# overall_circuit.net
KiCad netlist of a schematic drawn in EAGLE
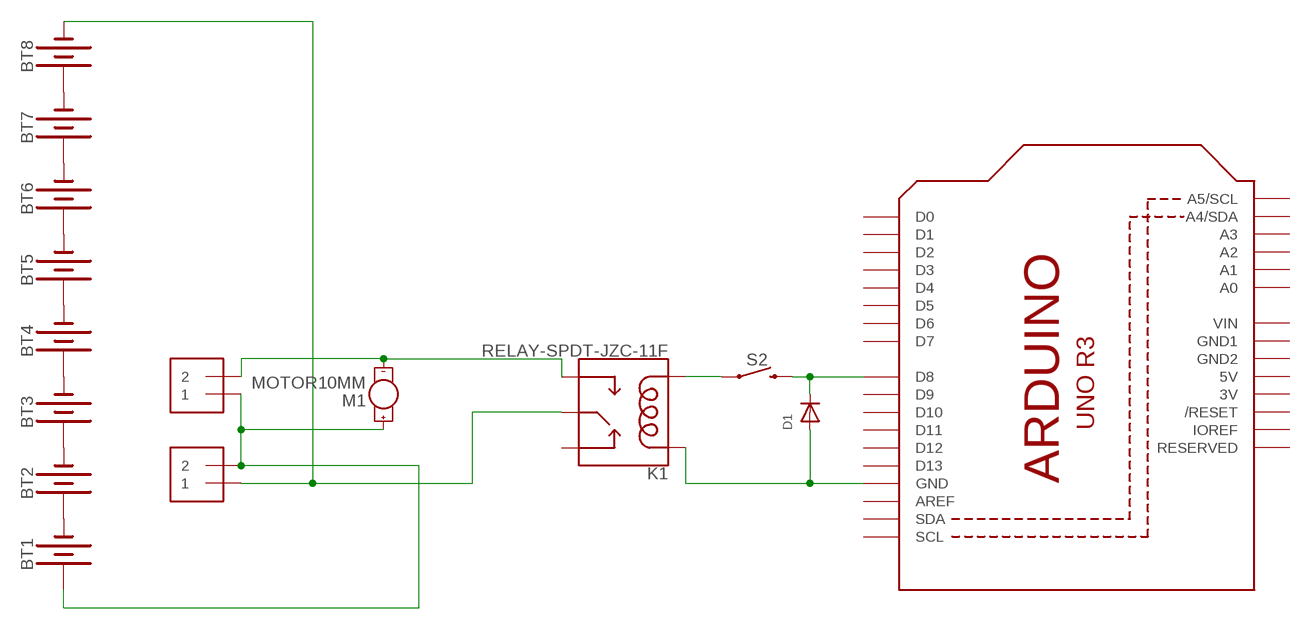
[diagram p0: schematic, sheet 1]

(export (version "E")
  (design (tool "Eeschema 10.0.6"))
  (components
    (comp (ref "BT1")
      (value "BATTERY-9V")
      (footprint "eagle-import:BATTCON_9V")
      (libsource (lib "eagle-import") (part "BATTERY-9V"))
    )
    (comp (ref "BT2")
      (value "BATTERY-9V")
      (footprint "eagle-import:BATTCON_9V")
      (libsource (lib "eagle-import") (part "BATTERY-9V"))
    )
    (comp (ref "BT3")
      (value "BATTERY-9V")
      (footprint "eagle-import:BATTCON_9V")
      (libsource (lib "eagle-import") (part "BATTERY-9V"))
    )
    (comp (ref "BT4")
      (value "BATTERY-9V")
      (footprint "eagle-import:BATTCON_9V")
      (libsource (lib "eagle-import") (part "BATTERY-9V"))
    )
    (comp (ref "BT5")
      (value "BATTERY-9V")
      (footprint "eagle-import:BATTCON_9V")
      (libsource (lib "eagle-import") (part "BATTERY-9V"))
    )
    (comp (ref "BT6")
      (value "BATTERY-9V")
      (footprint "eagle-import:BATTCON_9V")
      (libsource (lib "eagle-import") (part "BATTERY-9V"))
    )
    (comp (ref "BT7")
      (value "BATTERY-9V")
      (footprint "eagle-import:BATTCON_9V")
      (libsource (lib "eagle-import") (part "BATTERY-9V"))
    )
    (comp (ref "BT8")
      (value "BATTERY-9V")
      (footprint "eagle-import:BATTCON_9V")
      (libsource (lib "eagle-import") (part "BATTERY-9V"))
    )
    (comp (ref "D1")
      (value "DIODEDO-1N4148")
      (footprint "eagle-import:DO-1N4148")
      (libsource (lib "eagle-import") (part "DIODEDO-1N4148"))
    )
    (comp (ref "J1")
      (value "1X2-3.5MM")
      (footprint "eagle-import:1X2-3.5MM")
      (libsource (lib "eagle-import") (part "1X2-3.5MM"))
    )
    (comp (ref "J2")
      (value "1X2-3.5MM")
      (footprint "eagle-import:1X2-3.5MM")
      (libsource (lib "eagle-import") (part "1X2-3.5MM"))
    )
    (comp (ref "K1")
      (value "RELAY-SPDT-JZC-11F")
      (footprint "eagle-import:RELAY-JZC")
      (libsource (lib "eagle-import") (part "RELAY-SPDT-JZC-11F"))
    )
    (comp (ref "M1")
      (value "MOTOR10MM")
      (footprint "eagle-import:VIBE-MOTOR-10MM")
      (libsource (lib "eagle-import") (part "MOTOR10MM"))
    )
    (comp (ref "S2")
      (value "MOMENTARY-SWITCH-SPST-SMD-5.2MM")
      (footprint "eagle-import:TACTILE_SWITCH_SMD_5.2MM")
      (libsource (lib "eagle-import") (part "MOMENTARY-SWITCH-SPST-SMD-5.2MM"))
    )
    (comp (ref "U1")
      (value "ARDUINOR3-DIMENSION")
      (footprint "eagle-import:ARDUINOR3")
      (libsource (lib "eagle-import") (part "ARDUINOR3-DIMENSION"))
    )
  )
  (nets
    (net (code "1") (name "/3V") (class "Default")
      (node (ref "U1") (pin "3V") (pinfunction "3V_3V") (pintype "power_in"))
    )
    (net (code "2") (name "/5V") (class "Default")
      (node (ref "U1") (pin "5V") (pinfunction "5V_5V") (pintype "power_in"))
    )
    (net (code "3") (name "/GND1") (class "Default")
      (node (ref "U1") (pin "GND1") (pinfunction "GND1_GND1") (pintype "power_in"))
    )
    (net (code "4") (name "/GND2") (class "Default")
      (node (ref "U1") (pin "GND2") (pinfunction "GND2_GND2") (pintype "power_in"))
    )
    (net (code "5") (name "/VIN") (class "Default")
      (node (ref "U1") (pin "VIN") (pinfunction "VIN_VIN") (pintype "power_in"))
    )
    (net (code "6") (name "Net-(BT1-Pad+)") (class "Default")
      (node (ref "BT1") (pin "+") (pinfunction "+_+") (pintype "power_in"))
      (node (ref "J1") (pin "1") (pinfunction "1_1") (pintype "passive"))
      (node (ref "J2") (pin "2") (pinfunction "2_2") (pintype "passive"))
      (node (ref "M1") (pin "+") (pinfunction "+_+") (pintype "bidirectional"))
    )
    (net (code "7") (name "Net-(BT1-Pad-)") (class "Default")
      (node (ref "BT1") (pin "-") (pinfunction "-_-") (pintype "power_in"))
      (node (ref "BT2") (pin "+") (pinfunction "+_+") (pintype "power_in"))
    )
    (net (code "8") (name "Net-(BT2-Pad-)") (class "Default")
      (node (ref "BT2") (pin "-") (pinfunction "-_-") (pintype "power_in"))
      (node (ref "BT3") (pin "+") (pinfunction "+_+") (pintype "power_in"))
    )
    (net (code "9") (name "Net-(BT3-Pad-)") (class "Default")
      (node (ref "BT3") (pin "-") (pinfunction "-_-") (pintype "power_in"))
      (node (ref "BT4") (pin "+") (pinfunction "+_+") (pintype "power_in"))
    )
    (net (code "10") (name "Net-(BT4-Pad-)") (class "Default")
      (node (ref "BT4") (pin "-") (pinfunction "-_-") (pintype "power_in"))
      (node (ref "BT5") (pin "+") (pinfunction "+_+") (pintype "power_in"))
    )
    (net (code "11") (name "Net-(BT5-Pad-)") (class "Default")
      (node (ref "BT5") (pin "-") (pinfunction "-_-") (pintype "power_in"))
      (node (ref "BT6") (pin "+") (pinfunction "+_+") (pintype "power_in"))
    )
    (net (code "12") (name "Net-(BT6-Pad-)") (class "Default")
      (node (ref "BT6") (pin "-") (pinfunction "-_-") (pintype "power_in"))
      (node (ref "BT7") (pin "+") (pinfunction "+_+") (pintype "power_in"))
    )
    (net (code "13") (name "Net-(BT7-Pad-)") (class "Default")
      (node (ref "BT7") (pin "-") (pinfunction "-_-") (pintype "power_in"))
      (node (ref "BT8") (pin "+") (pinfunction "+_+") (pintype "power_in"))
    )
    (net (code "14") (name "Net-(K1-COIL1)") (class "Default")
      (node (ref "D1") (pin "A") (pinfunction "A_A") (pintype "passive"))
      (node (ref "K1") (pin "5") (pinfunction "COIL1_5") (pintype "bidirectional"))
      (node (ref "U1") (pin "GND") (pinfunction "GND_GND") (pintype "power_in"))
    )
    (net (code "15") (name "Net-(K1-COIL2)") (class "Default")
      (node (ref "K1") (pin "1") (pinfunction "COIL2_1") (pintype "bidirectional"))
      (node (ref "S2") (pin "1") (pinfunction "1_1") (pintype "passive"))
    )
    (net (code "16") (name "Net-(K1-MAIN)") (class "Default")
      (node (ref "BT8") (pin "-") (pinfunction "-_-") (pintype "power_in"))
      (node (ref "J2") (pin "1") (pinfunction "1_1") (pintype "passive"))
      (node (ref "K1") (pin "4") (pinfunction "MAIN_4") (pintype "bidirectional"))
    )
    (net (code "17") (name "Net-(K1-NO)") (class "Default")
      (node (ref "J1") (pin "2") (pinfunction "2_2") (pintype "passive"))
      (node (ref "K1") (pin "3") (pinfunction "NO_3") (pintype "bidirectional"))
      (node (ref "M1") (pin "-") (pinfunction "-_-") (pintype "bidirectional"))
    )
    (net (code "18") (name "Net-(S2-2)") (class "Default")
      (node (ref "D1") (pin "C") (pinfunction "C_C") (pintype "passive"))
      (node (ref "S2") (pin "3") (pinfunction "2_3") (pintype "passive"))
      (node (ref "U1") (pin "D8") (pinfunction "D8_D8") (pintype "bidirectional"))
    )
    (net (code "19") (name "unconnected-(K1-NC-Pad2)") (class "Default")
      (node (ref "K1") (pin "2") (pinfunction "NC_2") (pintype "bidirectional"))
    )
    (net (code "20") (name "unconnected-(U1-A4{slash}SDA-PadA4)") (class "Default")
      (node (ref "U1") (pin "A4") (pinfunction "A4/SDA_A4") (pintype "bidirectional"))
    )
    (net (code "21") (name "unconnected-(U1-A5{slash}SCL-PadA5)") (class "Default")
      (node (ref "U1") (pin "A5") (pinfunction "A5/SCL_A5") (pintype "bidirectional"))
    )
    (net (code "22") (name "unconnected-(U1-PadA0)") (class "Default")
      (node (ref "U1") (pin "A0") (pinfunction "A0_A0") (pintype "bidirectional"))
    )
    (net (code "23") (name "unconnected-(U1-PadA1)") (class "Default")
      (node (ref "U1") (pin "A1") (pinfunction "A1_A1") (pintype "bidirectional"))
    )
    (net (code "24") (name "unconnected-(U1-PadA2)") (class "Default")
      (node (ref "U1") (pin "A2") (pinfunction "A2_A2") (pintype "bidirectional"))
    )
    (net (code "25") (name "unconnected-(U1-PadA3)") (class "Default")
      (node (ref "U1") (pin "A3") (pinfunction "A3_A3") (pintype "bidirectional"))
    )
    (net (code "26") (name "unconnected-(U1-PadAREF)") (class "Default")
      (node (ref "U1") (pin "AREF") (pinfunction "AREF_AREF") (pintype "bidirectional"))
    )
    (net (code "27") (name "unconnected-(U1-PadD0)") (class "Default")
      (node (ref "U1") (pin "D0") (pinfunction "D0_D0") (pintype "bidirectional"))
    )
    (net (code "28") (name "unconnected-(U1-PadD1)") (class "Default")
      (node (ref "U1") (pin "D1") (pinfunction "D1_D1") (pintype "bidirectional"))
    )
    (net (code "29") (name "unconnected-(U1-PadD2)") (class "Default")
      (node (ref "U1") (pin "D2") (pinfunction "D2_D2") (pintype "bidirectional"))
    )
    (net (code "30") (name "unconnected-(U1-PadD3)") (class "Default")
      (node (ref "U1") (pin "D3") (pinfunction "D3_D3") (pintype "bidirectional"))
    )
    (net (code "31") (name "unconnected-(U1-PadD4)") (class "Default")
      (node (ref "U1") (pin "D4") (pinfunction "D4_D4") (pintype "bidirectional"))
    )
    (net (code "32") (name "unconnected-(U1-PadD5)") (class "Default")
      (node (ref "U1") (pin "D5") (pinfunction "D5_D5") (pintype "bidirectional"))
    )
    (net (code "33") (name "unconnected-(U1-PadD6)") (class "Default")
      (node (ref "U1") (pin "D6") (pinfunction "D6_D6") (pintype "bidirectional"))
    )
    (net (code "34") (name "unconnected-(U1-PadD7)") (class "Default")
      (node (ref "U1") (pin "D7") (pinfunction "D7_D7") (pintype "bidirectional"))
    )
    (net (code "35") (name "unconnected-(U1-PadD9)") (class "Default")
      (node (ref "U1") (pin "D9") (pinfunction "D9_D9") (pintype "bidirectional"))
    )
    (net (code "36") (name "unconnected-(U1-PadD10)") (class "Default")
      (node (ref "U1") (pin "D10") (pinfunction "D10_D10") (pintype "bidirectional"))
    )
    (net (code "37") (name "unconnected-(U1-PadD11)") (class "Default")
      (node (ref "U1") (pin "D11") (pinfunction "D11_D11") (pintype "bidirectional"))
    )
    (net (code "38") (name "unconnected-(U1-PadD12)") (class "Default")
      (node (ref "U1") (pin "D12") (pinfunction "D12_D12") (pintype "bidirectional"))
    )
    (net (code "39") (name "unconnected-(U1-PadD13)") (class "Default")
      (node (ref "U1") (pin "D13") (pinfunction "D13_D13") (pintype "bidirectional"))
    )
    (net (code "40") (name "unconnected-(U1-PadIOREF)") (class "Default")
      (node (ref "U1") (pin "IOREF") (pinfunction "IOREF_IOREF") (pintype "output"))
    )
    (net (code "41") (name "unconnected-(U1-PadRESERVED)") (class "Default")
      (node (ref "U1") (pin "RESERVED") (pinfunction "RESERVED_RESERVED") (pintype "no_connect"))
    )
    (net (code "42") (name "unconnected-(U1-PadSCL)") (class "Default")
      (node (ref "U1") (pin "SCL") (pinfunction "SCL_SCL") (pintype "bidirectional"))
    )
    (net (code "43") (name "unconnected-(U1-PadSDA)") (class "Default")
      (node (ref "U1") (pin "SDA") (pinfunction "SDA_SDA") (pintype "bidirectional"))
    )
    (net (code "44") (name "unconnected-(U1-{slash}RESET-PadRESET)") (class "Default")
      (node (ref "U1") (pin "RESET") (pinfunction "/RESET_RESET") (pintype "bidirectional"))
    )
  )
)
